# uno_bt.net
KiCad netlist of a schematic drawn in EAGLE
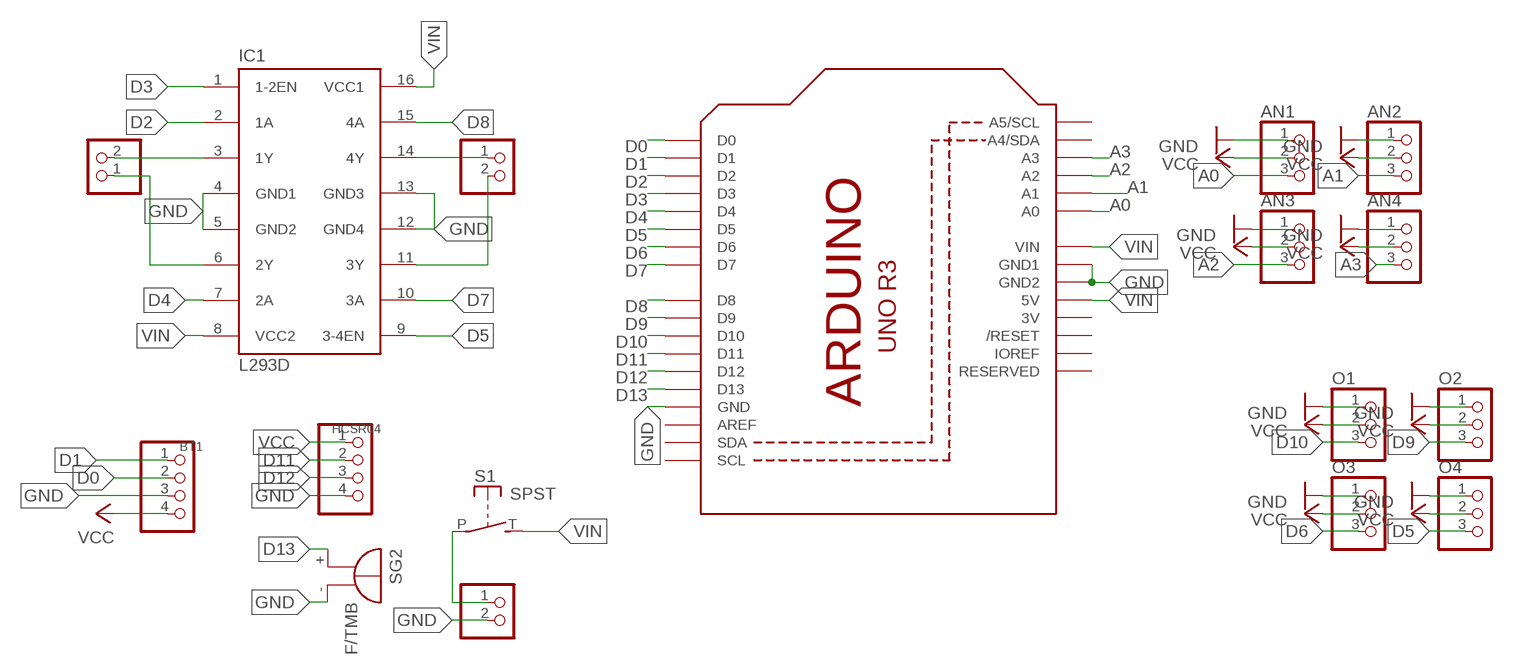
[diagram p0: schematic, sheet 1]

(export (version "E")
  (design (tool "Eeschema 10.0.6"))
  (components
    (comp (ref "AN1")
      (value "PINHD-1X3")
      (footprint "eagle-import:1X03")
      (libsource (lib "eagle-import") (part "PINHD-1X3"))
    )
    (comp (ref "AN2")
      (value "PINHD-1X3")
      (footprint "eagle-import:1X03")
      (libsource (lib "eagle-import") (part "PINHD-1X3"))
    )
    (comp (ref "AN3")
      (value "PINHD-1X3")
      (footprint "eagle-import:1X03")
      (libsource (lib "eagle-import") (part "PINHD-1X3"))
    )
    (comp (ref "AN4")
      (value "PINHD-1X3")
      (footprint "eagle-import:1X03")
      (libsource (lib "eagle-import") (part "PINHD-1X3"))
    )
    (comp (ref "BT1")
      (value "PINHD-1X4")
      (footprint "eagle-import:1X04")
      (libsource (lib "eagle-import") (part "PINHD-1X4"))
    )
    (comp (ref "DCIN")
      (value "PINHD-1X2")
      (footprint "eagle-import:1X02")
      (libsource (lib "eagle-import") (part "PINHD-1X2"))
    )
    (comp (ref "HCSR04")
      (value "PINHD-1X4")
      (footprint "eagle-import:1X04")
      (libsource (lib "eagle-import") (part "PINHD-1X4"))
    )
    (comp (ref "IC1")
      (value "L293D")
      (footprint "eagle-import:DIL16")
      (libsource (lib "eagle-import") (part "L293D"))
    )
    (comp (ref "MT1")
      (value "PINHD-1X2")
      (footprint "eagle-import:1X02")
      (libsource (lib "eagle-import") (part "PINHD-1X2"))
    )
    (comp (ref "MT2")
      (value "PINHD-1X2")
      (footprint "eagle-import:1X02")
      (libsource (lib "eagle-import") (part "PINHD-1X2"))
    )
    (comp (ref "O1")
      (value "PINHD-1X3")
      (footprint "eagle-import:1X03")
      (libsource (lib "eagle-import") (part "PINHD-1X3"))
    )
    (comp (ref "O2")
      (value "PINHD-1X3")
      (footprint "eagle-import:1X03")
      (libsource (lib "eagle-import") (part "PINHD-1X3"))
    )
    (comp (ref "O3")
      (value "PINHD-1X3")
      (footprint "eagle-import:1X03")
      (libsource (lib "eagle-import") (part "PINHD-1X3"))
    )
    (comp (ref "O4")
      (value "PINHD-1X3")
      (footprint "eagle-import:1X03")
      (libsource (lib "eagle-import") (part "PINHD-1X3"))
    )
    (comp (ref "S1")
      (value "SPST")
      (footprint "eagle-import:JUDCOSPST")
      (libsource (lib "eagle-import") (part "SPST"))
    )
    (comp (ref "SG2")
      (value "F/TMB")
      (footprint "eagle-import:F_TMB")
      (libsource (lib "eagle-import") (part "F/TMB"))
    )
    (comp (ref "U1")
      (value "ARDUINOR3-BPLACE")
      (footprint "eagle-import:ARDUINOR3-BPLACE")
      (libsource (lib "eagle-import") (part "ARDUINOR3-BPLACE"))
    )
  )
  (nets
    (net (code "1") (name "/3V") (class "Default")
      (node (ref "U1") (pin "3V") (pinfunction "3V_3V") (pintype "power_in"))
    )
    (net (code "2") (name "A0") (class "Default")
      (node (ref "AN1") (pin "3") (pinfunction "3_3") (pintype "passive"))
      (node (ref "U1") (pin "A0") (pinfunction "A0_A0") (pintype "bidirectional"))
    )
    (net (code "3") (name "A1") (class "Default")
      (node (ref "AN2") (pin "3") (pinfunction "3_3") (pintype "passive"))
      (node (ref "U1") (pin "A1") (pinfunction "A1_A1") (pintype "bidirectional"))
    )
    (net (code "4") (name "A2") (class "Default")
      (node (ref "AN3") (pin "3") (pinfunction "3_3") (pintype "passive"))
      (node (ref "U1") (pin "A2") (pinfunction "A2_A2") (pintype "bidirectional"))
    )
    (net (code "5") (name "A3") (class "Default")
      (node (ref "AN4") (pin "3") (pinfunction "3_3") (pintype "passive"))
      (node (ref "U1") (pin "A3") (pinfunction "A3_A3") (pintype "bidirectional"))
    )
    (net (code "6") (name "D0") (class "Default")
      (node (ref "BT1") (pin "2") (pinfunction "2_2") (pintype "passive"))
      (node (ref "U1") (pin "D0") (pinfunction "D0_D0") (pintype "bidirectional"))
    )
    (net (code "7") (name "D1") (class "Default")
      (node (ref "BT1") (pin "1") (pinfunction "1_1") (pintype "passive"))
      (node (ref "U1") (pin "D1") (pinfunction "D1_D1") (pintype "bidirectional"))
    )
    (net (code "8") (name "D2") (class "Default")
      (node (ref "IC1") (pin "2") (pinfunction "1A_2") (pintype "input"))
      (node (ref "U1") (pin "D2") (pinfunction "D2_D2") (pintype "bidirectional"))
    )
    (net (code "9") (name "D3") (class "Default")
      (node (ref "IC1") (pin "1") (pinfunction "1-2EN_1") (pintype "input"))
      (node (ref "U1") (pin "D3") (pinfunction "D3_D3") (pintype "bidirectional"))
    )
    (net (code "10") (name "D4") (class "Default")
      (node (ref "IC1") (pin "7") (pinfunction "2A_7") (pintype "input"))
      (node (ref "U1") (pin "D4") (pinfunction "D4_D4") (pintype "bidirectional"))
    )
    (net (code "11") (name "D5") (class "Default")
      (node (ref "IC1") (pin "9") (pinfunction "3-4EN_9") (pintype "input"))
      (node (ref "O4") (pin "3") (pinfunction "3_3") (pintype "passive"))
      (node (ref "U1") (pin "D5") (pinfunction "D5_D5") (pintype "bidirectional"))
    )
    (net (code "12") (name "D6") (class "Default")
      (node (ref "O3") (pin "3") (pinfunction "3_3") (pintype "passive"))
      (node (ref "U1") (pin "D6") (pinfunction "D6_D6") (pintype "bidirectional"))
    )
    (net (code "13") (name "D7") (class "Default")
      (node (ref "IC1") (pin "10") (pinfunction "3A_10") (pintype "input"))
      (node (ref "U1") (pin "D7") (pinfunction "D7_D7") (pintype "bidirectional"))
    )
    (net (code "14") (name "D8") (class "Default")
      (node (ref "IC1") (pin "15") (pinfunction "4A_15") (pintype "input"))
      (node (ref "U1") (pin "D8") (pinfunction "D8_D8") (pintype "bidirectional"))
    )
    (net (code "15") (name "D9") (class "Default")
      (node (ref "O2") (pin "3") (pinfunction "3_3") (pintype "passive"))
      (node (ref "U1") (pin "D9") (pinfunction "D9_D9") (pintype "bidirectional"))
    )
    (net (code "16") (name "D10") (class "Default")
      (node (ref "O1") (pin "3") (pinfunction "3_3") (pintype "passive"))
      (node (ref "U1") (pin "D10") (pinfunction "D10_D10") (pintype "bidirectional"))
    )
    (net (code "17") (name "D11") (class "Default")
      (node (ref "HCSR04") (pin "2") (pinfunction "2_2") (pintype "passive"))
      (node (ref "U1") (pin "D11") (pinfunction "D11_D11") (pintype "bidirectional"))
    )
    (net (code "18") (name "D12") (class "Default")
      (node (ref "HCSR04") (pin "3") (pinfunction "3_3") (pintype "passive"))
      (node (ref "U1") (pin "D12") (pinfunction "D12_D12") (pintype "bidirectional"))
    )
    (net (code "19") (name "D13") (class "Default")
      (node (ref "SG2") (pin "+") (pinfunction "+_+") (pintype "passive"))
      (node (ref "U1") (pin "D13") (pinfunction "D13_D13") (pintype "bidirectional"))
    )
    (net (code "20") (name "GND") (class "Default")
      (node (ref "AN1") (pin "1") (pinfunction "1_1") (pintype "passive"))
      (node (ref "AN2") (pin "1") (pinfunction "1_1") (pintype "passive"))
      (node (ref "AN3") (pin "1") (pinfunction "1_1") (pintype "passive"))
      (node (ref "AN4") (pin "1") (pinfunction "1_1") (pintype "passive"))
      (node (ref "BT1") (pin "3") (pinfunction "3_3") (pintype "passive"))
      (node (ref "DCIN") (pin "2") (pinfunction "2_2") (pintype "passive"))
      (node (ref "HCSR04") (pin "4") (pinfunction "4_4") (pintype "passive"))
      (node (ref "IC1") (pin "12") (pinfunction "GND4_12") (pintype "power_in"))
      (node (ref "IC1") (pin "13") (pinfunction "GND3_13") (pintype "power_in"))
      (node (ref "IC1") (pin "4") (pinfunction "GND1_4") (pintype "power_in"))
      (node (ref "IC1") (pin "5") (pinfunction "GND2_5") (pintype "power_in"))
      (node (ref "O1") (pin "1") (pinfunction "1_1") (pintype "passive"))
      (node (ref "O2") (pin "1") (pinfunction "1_1") (pintype "passive"))
      (node (ref "O3") (pin "1") (pinfunction "1_1") (pintype "passive"))
      (node (ref "O4") (pin "1") (pinfunction "1_1") (pintype "passive"))
      (node (ref "SG2") (pin "-") (pinfunction "-_-") (pintype "passive"))
      (node (ref "U1") (pin "GND") (pinfunction "GND_GND") (pintype "power_in"))
      (node (ref "U1") (pin "GND1") (pinfunction "GND1_GND1") (pintype "power_in"))
      (node (ref "U1") (pin "GND2") (pinfunction "GND2_GND2") (pintype "power_in"))
    )
    (net (code "21") (name "Net-(DCIN-Pad1)") (class "Default")
      (node (ref "DCIN") (pin "1") (pinfunction "1_1") (pintype "passive"))
      (node (ref "S1") (pin "P") (pinfunction "P_P") (pintype "passive"))
    )
    (net (code "22") (name "Net-(IC1-1Y)") (class "Default")
      (node (ref "IC1") (pin "3") (pinfunction "1Y_3") (pintype "output"))
      (node (ref "MT1") (pin "2") (pinfunction "2_2") (pintype "passive"))
    )
    (net (code "23") (name "Net-(IC1-2Y)") (class "Default")
      (node (ref "IC1") (pin "6") (pinfunction "2Y_6") (pintype "output"))
      (node (ref "MT1") (pin "1") (pinfunction "1_1") (pintype "passive"))
    )
    (net (code "24") (name "Net-(IC1-3Y)") (class "Default")
      (node (ref "IC1") (pin "11") (pinfunction "3Y_11") (pintype "output"))
      (node (ref "MT2") (pin "2") (pinfunction "2_2") (pintype "passive"))
    )
    (net (code "25") (name "Net-(IC1-4Y)") (class "Default")
      (node (ref "IC1") (pin "14") (pinfunction "4Y_14") (pintype "output"))
      (node (ref "MT2") (pin "1") (pinfunction "1_1") (pintype "passive"))
    )
    (net (code "26") (name "VCC") (class "Default")
      (node (ref "AN1") (pin "2") (pinfunction "2_2") (pintype "passive"))
      (node (ref "AN2") (pin "2") (pinfunction "2_2") (pintype "passive"))
      (node (ref "AN3") (pin "2") (pinfunction "2_2") (pintype "passive"))
      (node (ref "AN4") (pin "2") (pinfunction "2_2") (pintype "passive"))
      (node (ref "BT1") (pin "4") (pinfunction "4_4") (pintype "passive"))
      (node (ref "HCSR04") (pin "1") (pinfunction "1_1") (pintype "passive"))
      (node (ref "O1") (pin "2") (pinfunction "2_2") (pintype "passive"))
      (node (ref "O2") (pin "2") (pinfunction "2_2") (pintype "passive"))
      (node (ref "O3") (pin "2") (pinfunction "2_2") (pintype "passive"))
      (node (ref "O4") (pin "2") (pinfunction "2_2") (pintype "passive"))
    )
    (net (code "27") (name "VIN") (class "Default")
      (node (ref "IC1") (pin "16") (pinfunction "VCC1_16") (pintype "power_in"))
      (node (ref "IC1") (pin "8") (pinfunction "VCC2_8") (pintype "power_in"))
      (node (ref "S1") (pin "T") (pinfunction "S_T") (pintype "passive"))
      (node (ref "U1") (pin "5V") (pinfunction "5V_5V") (pintype "power_in"))
      (node (ref "U1") (pin "VIN") (pinfunction "VIN_VIN") (pintype "power_in"))
    )
    (net (code "28") (name "unconnected-(U1-A4{slash}SDA-PadA4)") (class "Default")
      (node (ref "U1") (pin "A4") (pinfunction "A4/SDA_A4") (pintype "bidirectional"))
    )
    (net (code "29") (name "unconnected-(U1-A5{slash}SCL-PadA5)") (class "Default")
      (node (ref "U1") (pin "A5") (pinfunction "A5/SCL_A5") (pintype "bidirectional"))
    )
    (net (code "30") (name "unconnected-(U1-PadAREF)") (class "Default")
      (node (ref "U1") (pin "AREF") (pinfunction "AREF_AREF") (pintype "bidirectional"))
    )
    (net (code "31") (name "unconnected-(U1-PadIOREF)") (class "Default")
      (node (ref "U1") (pin "IOREF") (pinfunction "IOREF_IOREF") (pintype "output"))
    )
    (net (code "32") (name "unconnected-(U1-PadRESERVED)") (class "Default")
      (node (ref "U1") (pin "RESERVED") (pinfunction "RESERVED_RESERVED") (pintype "no_connect"))
    )
    (net (code "33") (name "unconnected-(U1-PadSCL)") (class "Default")
      (node (ref "U1") (pin "SCL") (pinfunction "SCL_SCL") (pintype "bidirectional"))
    )
    (net (code "34") (name "unconnected-(U1-PadSDA)") (class "Default")
      (node (ref "U1") (pin "SDA") (pinfunction "SDA_SDA") (pintype "bidirectional"))
    )
    (net (code "35") (name "unconnected-(U1-{slash}RESET-PadRESET)") (class "Default")
      (node (ref "U1") (pin "RESET") (pinfunction "/RESET_RESET") (pintype "bidirectional"))
    )
  )
)
